# LiPo_batteries_charger.net
KiCad netlist of a schematic drawn in Altium Designer
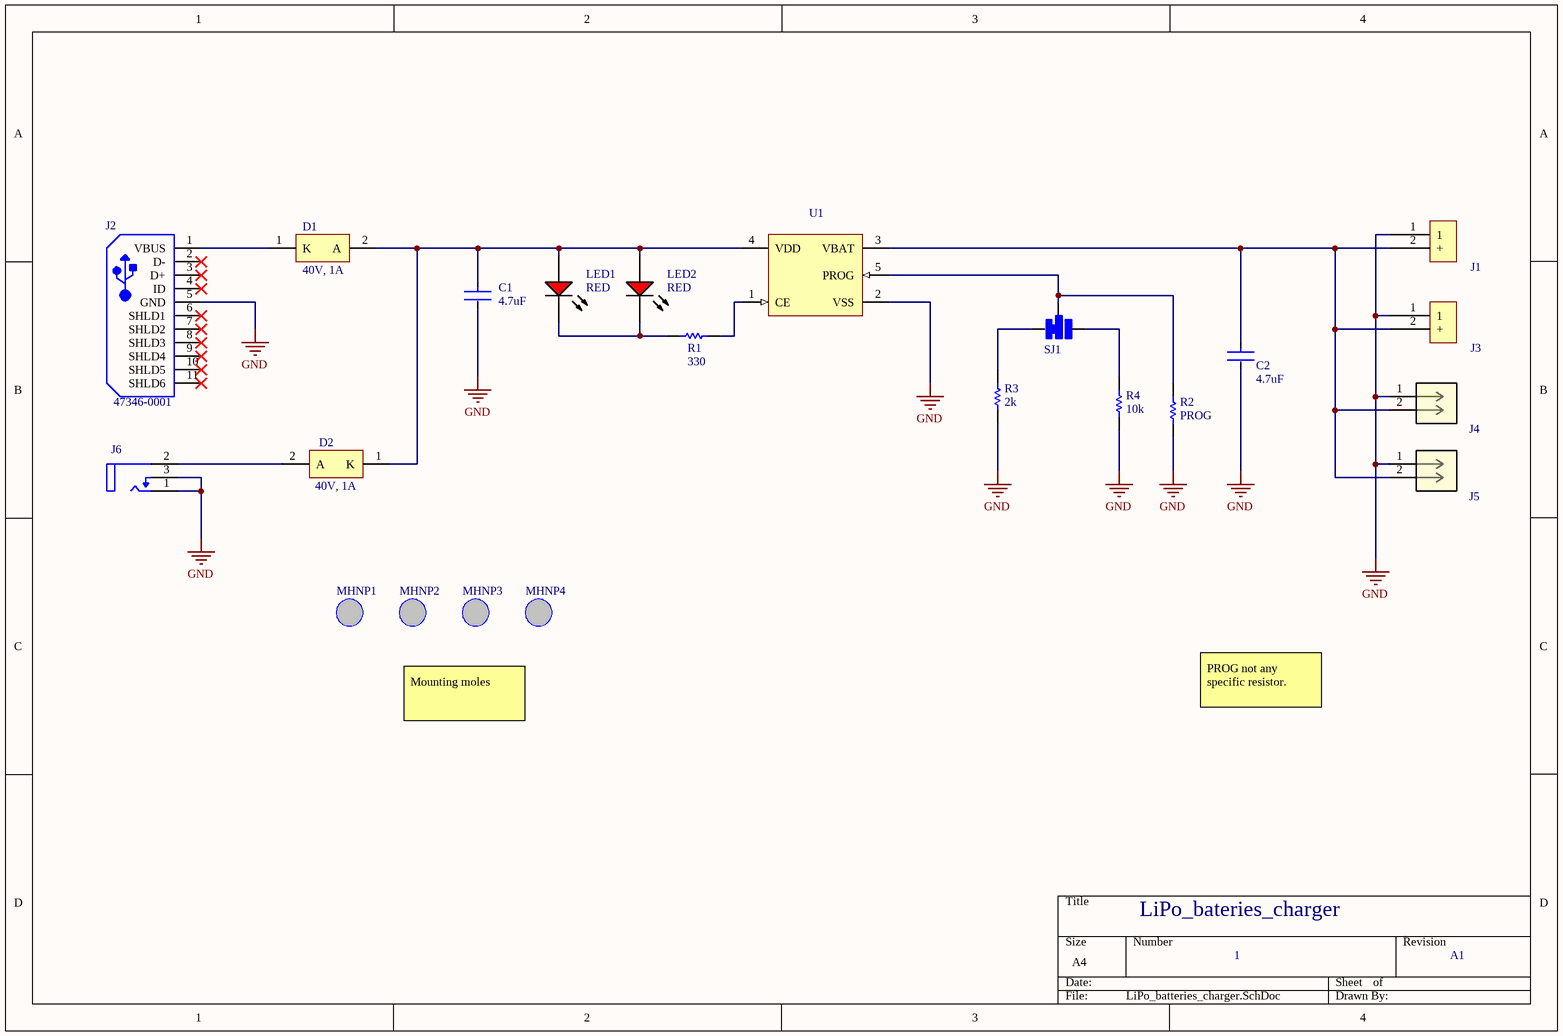
[diagram p0: LiPo_batteries_charger.SchDoc]

(export (version "E")
  (design (tool "Eeschema 10.0.6"))
  (components
    (comp (ref "C1")
      (value "4.7uF")
      (footprint "FP-CC0805-0_85-MFG")
      (description "4.7µF ±10% 6.3V Ceramic Capacitor X7R 0805 (2012 Metric)")
      (fields (field (name "MANUFACTURER") "Yageo") (field (name "TOLERANCE") "0.1"))
      (libsource (lib "LiPoBattery_A") (part "CAP CER 4.7UF 6.3V X7R 0805"))
    )
    (comp (ref "C2")
      (value "4.7uF")
      (footprint "FP-CC0805-0_85-MFG")
      (description "4.7µF ±10% 6.3V Ceramic Capacitor X7R 0805 (2012 Metric)")
      (fields (field (name "MANUFACTURER") "Yageo") (field (name "TOLERANCE") "0.1"))
      (libsource (lib "LiPoBattery_A") (part "CAP CER 4.7UF 6.3V X7R 0805"))
    )
    (comp (ref "D1")
      (value "40V, 1A")
      (footprint "ONSC-SMA-2-403D-02_V")
      (description "Schottky Power Rectifier, 2-Pin SMA, Pb-Free, Cut Tape, Diode Schottky 40V 1A Surface Mount SMA")
      (fields (field (name "PARTNUMBER") "MBRA140T3G") (field (name "MANUFACTURER") "ON Semiconductor"))
      (libsource (lib "") (part "DIODE SCHOTTKY 40V 1A SMA_1"))
    )
    (comp (ref "D2")
      (value "40V, 1A")
      (footprint "ONSC-SMA-2-403D-02_V")
      (description "Schottky Power Rectifier, 2-Pin SMA, Pb-Free, Cut Tape, Diode Schottky 40V 1A Surface Mount SMA")
      (fields (field (name "PARTNUMBER") "MBRA140T3G") (field (name "MANUFACTURER") "ON Semiconductor"))
      (libsource (lib "LiPoBattery_A") (part "DIODE SCHOTTKY 40V 1A SMA"))
    )
    (comp (ref "J1")
      (value "CONN HEADER R/A 2POS 5.08MM")
      (footprint "1-179276-2")
      (description "Connector Header Through Hole, Right Angle 2 position 0.200\" (5.08mm)")
      (fields
        (field (name "MANUFACTURER") "TE Connectivity AMP Connectors")
        (field (name "MANUFACTURER PART NUMBER") "1-179276-2")
      )
      (libsource (lib "LiPoBattery_A") (part "CONN HEADER R/A 2POS 5.08MM"))
    )
    (comp (ref "J2")
      (value "47346-0001")
      (footprint "MOLX-47346-0001-5_V")
      (description "Micro-USB B Receptacle with Flange, -30 to 85 degC, 5-Pin SMD, RoHS, Tape and Reel")
      (fields (field (name "MANUFACTURER") "Molex"))
      (libsource (lib "LiPoBattery_A") (part "CONN RCPT USB2.0 MICRO B SMD R/A"))
    )
    (comp (ref "J3")
      (value "CONN HEADER R/A 2POS 5.08MM")
      (footprint "1-179276-2")
      (description "Connector Header Through Hole, Right Angle 2 position 0.200\" (5.08mm)")
      (fields
        (field (name "MANUFACTURER") "TE Connectivity AMP Connectors")
        (field (name "MANUFACTURER PART NUMBER") "1-179276-2")
      )
      (libsource (lib "LiPoBattery_A") (part "CONN HEADER R/A 2POS 5.08MM"))
    )
    (comp (ref "J4")
      (value "2 POS VERT HEADER 0.100\"")
      (footprint "2Pins_AMP")
      (description "Connector Header Through Hole 2 position")
      (fields
        (field (name "MANUFACTURER PART NUMBER") "67997-402HLF")
        (field (name "MANUFACTURER") "Amphenol ICC (FCI)")
        (field (name "COPYRIGHT") "Copyright (C) 2018 Accelerated Designs. All rights reserved")
      )
      (libsource (lib "LiPoBattery_A") (part "CONN HEADER VERT 2POS 0.100{dblquote}"))
    )
    (comp (ref "J5")
      (value "2 POS VERT HEADER 0.100\"")
      (footprint "2Pins_AMP")
      (description "Connector Header Through Hole 2 position")
      (fields
        (field (name "MANUFACTURER PART NUMBER") "67997-402HLF")
        (field (name "MANUFACTURER") "Amphenol ICC (FCI)")
        (field (name "COPYRIGHT") "Copyright (C) 2018 Accelerated Designs. All rights reserved")
      )
      (libsource (lib "LiPoBattery_A") (part "CONN HEADER VERT 2POS 0.100{dblquote}"))
    )
    (comp (ref "J6")
      (value "RASM722PTR13X")
      (footprint "FP-RASM722PTR13X-MFG")
      (description "Power Barrel Connector Jack 2.10mm ID (0.083\"), 5.50mm OD (0.217\") Surface Mount, Right Angle")
      (fields (field (name "MANUFACTURER") "Switchcraft"))
      (libsource (lib "LiPoBattery_A") (part "CONN PWR JACK 2.1X5.5MM SOLDER"))
    )
    (comp (ref "LED1")
      (value "RED")
      (footprint "VISH-TLMS1000_V")
      (description "Low Current LED, 40 mW, 1.8 V, -40 to 100 degC, 2-Pin SMD (0603), RoHS, Tape and Reel")
      (fields
        (field (name "MANUFACTURER") "Vishay")
        (field (name "MANUFACTURER PART NUMBER") "TLMS1000-GS08")
      )
      (libsource (lib "LiPoBattery_A") (part "LED RED 0603 SMD"))
    )
    (comp (ref "LED2")
      (value "RED")
      (footprint "VISH-TLMS1000_V")
      (description "Low Current LED, 40 mW, 1.8 V, -40 to 100 degC, 2-Pin SMD (0603), RoHS, Tape and Reel")
      (fields
        (field (name "MANUFACTURER") "Vishay")
        (field (name "MANUFACTURER PART NUMBER") "TLMS1000-GS08")
      )
      (libsource (lib "LiPoBattery_A") (part "LED RED 0603 SMD"))
    )
    (comp (ref "MHNP1")
      (value "Mounting Hole Non-Plated 3.2mm")
      (footprint "MTHNP3P2MM")
      (description "Mounting Hole Non-Plated 3.2 mm drill hole")
      (libsource (lib "LiPoBattery_A") (part "MTHNP3P2MM"))
    )
    (comp (ref "MHNP2")
      (value "Mounting Hole Non-Plated 3.2mm")
      (footprint "MTHNP3P2MM")
      (description "Mounting Hole Non-Plated 3.2 mm drill hole")
      (libsource (lib "LiPoBattery_A") (part "MTHNP3P2MM"))
    )
    (comp (ref "MHNP3")
      (value "Mounting Hole Non-Plated 3.2mm")
      (footprint "MTHNP3P2MM")
      (description "Mounting Hole Non-Plated 3.2 mm drill hole")
      (libsource (lib "LiPoBattery_A") (part "MTHNP3P2MM"))
    )
    (comp (ref "MHNP4")
      (value "Mounting Hole Non-Plated 3.2mm")
      (footprint "MTHNP3P2MM")
      (description "Mounting Hole Non-Plated 3.2 mm drill hole")
      (libsource (lib "LiPoBattery_A") (part "MTHNP3P2MM"))
    )
    (comp (ref "R1")
      (value "330")
      (footprint "RESC2013X50X30NL20T20")
      (description "330 Ohms ±1% 0.125W, 1/8W Chip Resistor 0805 (2012 Metric) Automotive AEC-Q200 Thick Film")
      (fields
        (field (name "MANUFACTURER") "Vishay")
        (field (name "MANUFACTURER PART NUMBER") "CRCW0805330RFKEA")
      )
      (libsource (lib "LiPoBattery_A") (part "RES SMD 330 OHM 1% 1/8W 0805"))
    )
    (comp (ref "R2")
      (value "PROG")
      (footprint "VISH-A1-2_V2")
      (fields
        (field (name "TOLERANCE") "+/-5%")
        (field (name "POWER") "2 W")
        (field (name "PARTNUMBER") "PR02000206202JA100")
      )
      (libsource (lib "LiPoBattery_A") (part "RES 62K OHM 2W 5% AXIAL"))
    )
    (comp (ref "R3")
      (value "2k")
      (footprint "RESC2013X70X40ML20T20")
      (description "2 kOhms ±5% 0.125W, 1/8W Chip Resistor 0805 (2012 Metric) Automotive AEC-Q200 Thick Film")
      (fields
        (field (name "MANUFACTURER") "Panasonic")
        (field (name "MANUFACTURER PART NUMBER") "ERJ-6GEYJ202V")
      )
      (libsource (lib "LiPoBattery_A") (part "RES SMD 2K OHM 5% 1/8W 0805"))
    )
    (comp (ref "R4")
      (value "10k")
      (footprint "RESC2013X70X40ML20T20")
      (description "10 kOhms ±1% 0.125W, 1/8W Chip Resistor 0805 (2012 Metric) Automotive AEC-Q200 Thick Film")
      (fields
        (field (name "MANUFACTURER") "Panasonic")
        (field (name "MANUFACTURER PART NUMBER") "ERJ-6ENF1002V")
      )
      (libsource (lib "LiPoBattery_A") (part "RES SMD 10K OHM 1% 1/8W 0805"))
    )
    (comp (ref "SJ1")
      (value "SJUMPER3POS")
      (footprint "SJUMPER3POS-Footprint-1")
      (description "Solder jumper 3 pads and pins")
      (libsource (lib "LiPoBattery_A") (part "SJUMPER3POS"))
    )
    (comp (ref "U1")
      (value "Charge Management Controller")
      (footprint "SOT-23-OT5_M")
      (fields
        (field (name "MANUFACTURER") "Microchip")
        (field (name "MANUFACTURER PART NUMBER") "MCP73811T-420I/OT")
      )
      (libsource (lib "LiPoBattery_A") (part "IC LI-ION/LI-POLY CTRLR SOT23-5"))
    )
  )
  (nets
    (net (code "1") (name "GND") (class "Default")
      (node (ref "C1") (pin "2") (pinfunction "2_2") (pintype "passive"))
      (node (ref "C2") (pin "2") (pinfunction "2_2") (pintype "passive"))
      (node (ref "J1") (pin "1") (pinfunction "1_1") (pintype "passive"))
      (node (ref "J2") (pin "5") (pinfunction "GND_5") (pintype "passive"))
      (node (ref "J3") (pin "1") (pinfunction "1_1") (pintype "passive"))
      (node (ref "J4") (pin "1") (pinfunction "1_1") (pintype "passive"))
      (node (ref "J5") (pin "1") (pinfunction "1_1") (pintype "passive"))
      (node (ref "J6") (pin "1") (pinfunction "TIP_TERMINAL(CENTER_PIN)_1") (pintype "passive"))
      (node (ref "J6") (pin "3") (pinfunction "SHUNT_TERMINAL_3") (pintype "passive"))
      (node (ref "R2") (pin "1") (pinfunction "1_1") (pintype "passive"))
      (node (ref "R3") (pin "2") (pinfunction "2_2") (pintype "passive"))
      (node (ref "R4") (pin "2") (pinfunction "2_2") (pintype "passive"))
      (node (ref "U1") (pin "2") (pinfunction "VSS_2") (pintype "power_in"))
    )
    (net (code "2") (name "Net-(D1-A)") (class "Default")
      (node (ref "C1") (pin "1") (pinfunction "1_1") (pintype "passive"))
      (node (ref "D1") (pin "2") (pinfunction "A_2") (pintype "passive"))
      (node (ref "D2") (pin "1") (pinfunction "K_1") (pintype "passive"))
      (node (ref "LED1") (pin "1") (pinfunction "A_1") (pintype "passive"))
      (node (ref "LED2") (pin "1") (pinfunction "A_1") (pintype "passive"))
      (node (ref "U1") (pin "4") (pinfunction "VDD_4") (pintype "power_in"))
    )
    (net (code "3") (name "Net-(D1-K)") (class "Default")
      (node (ref "D1") (pin "1") (pinfunction "K_1") (pintype "passive"))
      (node (ref "J2") (pin "1") (pinfunction "VBUS_1") (pintype "passive"))
    )
    (net (code "4") (name "Net-(D2-A)") (class "Default")
      (node (ref "D2") (pin "2") (pinfunction "A_2") (pintype "passive"))
      (node (ref "J6") (pin "2") (pinfunction "SLEEVE_TERMINAL_2") (pintype "passive"))
    )
    (net (code "5") (name "Net-(J1-+)") (class "Default")
      (node (ref "C2") (pin "1") (pinfunction "1_1") (pintype "passive"))
      (node (ref "J1") (pin "2") (pinfunction "+_2") (pintype "passive"))
      (node (ref "J3") (pin "2") (pinfunction "+_2") (pintype "passive"))
      (node (ref "J4") (pin "2") (pinfunction "2_2") (pintype "passive"))
      (node (ref "J5") (pin "2") (pinfunction "2_2") (pintype "passive"))
      (node (ref "U1") (pin "3") (pinfunction "VBAT_3") (pintype "power_in"))
    )
    (net (code "6") (name "Net-(LED1-K)") (class "Default")
      (node (ref "LED1") (pin "2") (pinfunction "K_2") (pintype "passive"))
      (node (ref "LED2") (pin "2") (pinfunction "K_2") (pintype "passive"))
      (node (ref "R1") (pin "1") (pinfunction "1_1") (pintype "passive"))
    )
    (net (code "7") (name "Net-(R3-Pad1)") (class "Default")
      (node (ref "R3") (pin "1") (pinfunction "1_1") (pintype "passive"))
      (node (ref "SJ1") (pin "1") (pinfunction "1_1") (pintype "passive"))
    )
    (net (code "8") (name "Net-(R4-Pad1)") (class "Default")
      (node (ref "R4") (pin "1") (pinfunction "1_1") (pintype "passive"))
      (node (ref "SJ1") (pin "3") (pinfunction "3_3") (pintype "passive"))
    )
    (net (code "9") (name "Net-(U1-CE)") (class "Default")
      (node (ref "R1") (pin "2") (pinfunction "2_2") (pintype "passive"))
      (node (ref "U1") (pin "1") (pinfunction "CE_1") (pintype "input"))
    )
    (net (code "10") (name "Net-(U1-PROG)") (class "Default")
      (node (ref "R2") (pin "2") (pinfunction "2_2") (pintype "passive"))
      (node (ref "SJ1") (pin "2") (pinfunction "2_2") (pintype "passive"))
      (node (ref "U1") (pin "5") (pinfunction "PROG_5") (pintype "input"))
    )
    (net (code "11") (name "unconnected-(J2-D+-Pad3)") (class "Default")
      (node (ref "J2") (pin "3") (pinfunction "D+_3") (pintype "passive+no_connect"))
    )
    (net (code "12") (name "unconnected-(J2-D--Pad2)") (class "Default")
      (node (ref "J2") (pin "2") (pinfunction "D-_2") (pintype "passive+no_connect"))
    )
    (net (code "13") (name "unconnected-(J2-ID-Pad4)") (class "Default")
      (node (ref "J2") (pin "4") (pinfunction "ID_4") (pintype "passive+no_connect"))
    )
    (net (code "14") (name "unconnected-(J2-SHLD1-Pad6)") (class "Default")
      (node (ref "J2") (pin "6") (pinfunction "SHLD1_6") (pintype "passive+no_connect"))
    )
    (net (code "15") (name "unconnected-(J2-SHLD2-Pad7)") (class "Default")
      (node (ref "J2") (pin "7") (pinfunction "SHLD2_7") (pintype "passive+no_connect"))
    )
    (net (code "16") (name "unconnected-(J2-SHLD3-Pad8)") (class "Default")
      (node (ref "J2") (pin "8") (pinfunction "SHLD3_8") (pintype "passive+no_connect"))
    )
    (net (code "17") (name "unconnected-(J2-SHLD4-Pad9)") (class "Default")
      (node (ref "J2") (pin "9") (pinfunction "SHLD4_9") (pintype "passive+no_connect"))
    )
    (net (code "18") (name "unconnected-(J2-SHLD5-Pad10)") (class "Default")
      (node (ref "J2") (pin "10") (pinfunction "SHLD5_10") (pintype "passive+no_connect"))
    )
    (net (code "19") (name "unconnected-(J2-SHLD6-Pad11)") (class "Default")
      (node (ref "J2") (pin "11") (pinfunction "SHLD6_11") (pintype "passive+no_connect"))
    )
  )
)
